# LED_Matrix-2.net
KiCad netlist of a schematic drawn in Altium Designer
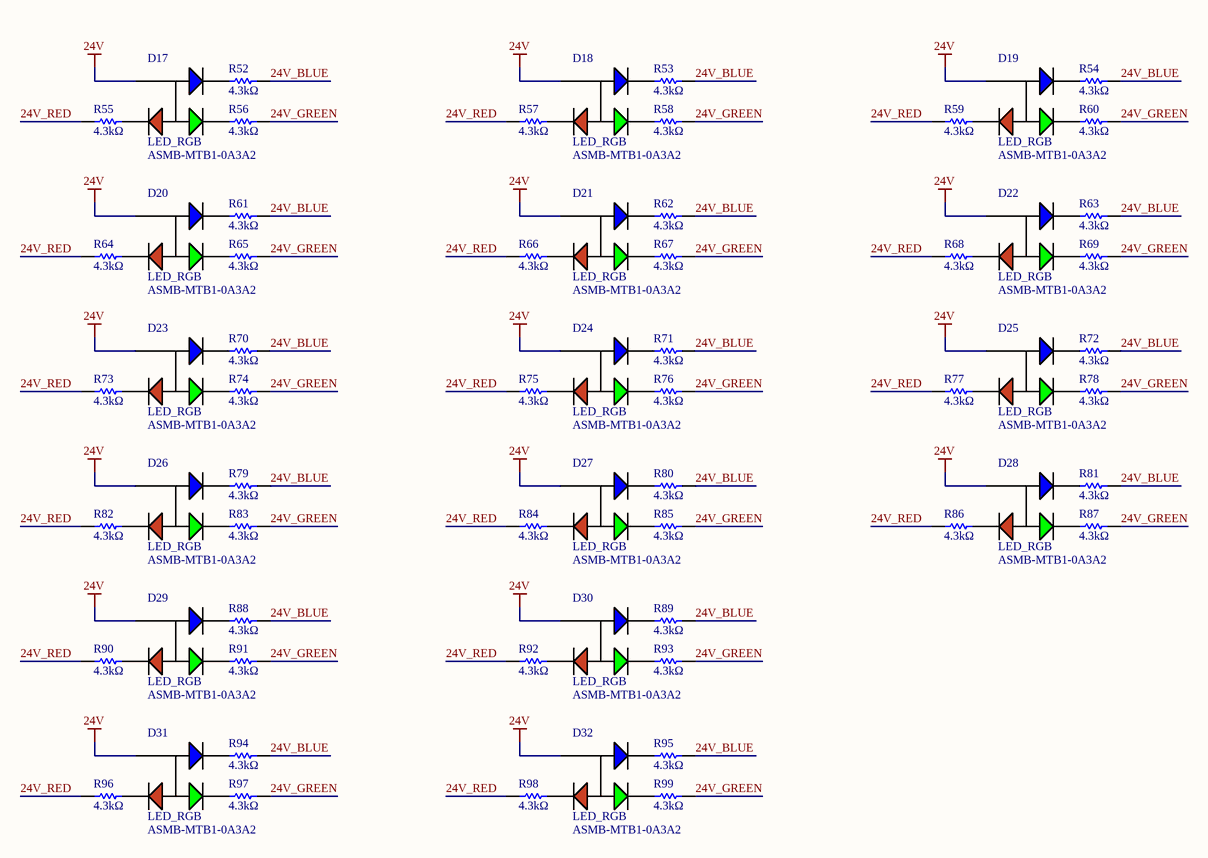
[diagram p0: LED Matrix-2.SchDoc]

(export (version "E")
  (design (tool "Eeschema 10.0.6"))
  (components
    (comp (ref "D17")
      (value "LED_RGB")
      (footprint "LED_RGB")
      (description "LED RGB DIFFUSED 4PLCC SMD")
      (fields (field (name "MANUFACTURER PART NUMBER 1") "ASMB-MTB1-0A3A2"))
      (libsource (lib "UWRT_Schematic_Library_2020") (part "LED_RGB"))
    )
    (comp (ref "D18")
      (value "LED_RGB")
      (footprint "LED_RGB")
      (description "LED RGB DIFFUSED 4PLCC SMD")
      (fields (field (name "MANUFACTURER PART NUMBER 1") "ASMB-MTB1-0A3A2"))
      (libsource (lib "UWRT_Schematic_Library_2020") (part "LED_RGB"))
    )
    (comp (ref "D19")
      (value "LED_RGB")
      (footprint "LED_RGB")
      (description "LED RGB DIFFUSED 4PLCC SMD")
      (fields (field (name "MANUFACTURER PART NUMBER 1") "ASMB-MTB1-0A3A2"))
      (libsource (lib "UWRT_Schematic_Library_2020") (part "LED_RGB"))
    )
    (comp (ref "D20")
      (value "LED_RGB")
      (footprint "LED_RGB")
      (description "LED RGB DIFFUSED 4PLCC SMD")
      (fields (field (name "MANUFACTURER PART NUMBER 1") "ASMB-MTB1-0A3A2"))
      (libsource (lib "UWRT_Schematic_Library_2020") (part "LED_RGB"))
    )
    (comp (ref "D21")
      (value "LED_RGB")
      (footprint "LED_RGB")
      (description "LED RGB DIFFUSED 4PLCC SMD")
      (fields (field (name "MANUFACTURER PART NUMBER 1") "ASMB-MTB1-0A3A2"))
      (libsource (lib "UWRT_Schematic_Library_2020") (part "LED_RGB"))
    )
    (comp (ref "D22")
      (value "LED_RGB")
      (footprint "LED_RGB")
      (description "LED RGB DIFFUSED 4PLCC SMD")
      (fields (field (name "MANUFACTURER PART NUMBER 1") "ASMB-MTB1-0A3A2"))
      (libsource (lib "UWRT_Schematic_Library_2020") (part "LED_RGB"))
    )
    (comp (ref "D23")
      (value "LED_RGB")
      (footprint "LED_RGB")
      (description "LED RGB DIFFUSED 4PLCC SMD")
      (fields (field (name "MANUFACTURER PART NUMBER 1") "ASMB-MTB1-0A3A2"))
      (libsource (lib "UWRT_Schematic_Library_2020") (part "LED_RGB"))
    )
    (comp (ref "D24")
      (value "LED_RGB")
      (footprint "LED_RGB")
      (description "LED RGB DIFFUSED 4PLCC SMD")
      (fields (field (name "MANUFACTURER PART NUMBER 1") "ASMB-MTB1-0A3A2"))
      (libsource (lib "UWRT_Schematic_Library_2020") (part "LED_RGB"))
    )
    (comp (ref "D25")
      (value "LED_RGB")
      (footprint "LED_RGB")
      (description "LED RGB DIFFUSED 4PLCC SMD")
      (fields (field (name "MANUFACTURER PART NUMBER 1") "ASMB-MTB1-0A3A2"))
      (libsource (lib "UWRT_Schematic_Library_2020") (part "LED_RGB"))
    )
    (comp (ref "D26")
      (value "LED_RGB")
      (footprint "LED_RGB")
      (description "LED RGB DIFFUSED 4PLCC SMD")
      (fields (field (name "MANUFACTURER PART NUMBER 1") "ASMB-MTB1-0A3A2"))
      (libsource (lib "UWRT_Schematic_Library_2020") (part "LED_RGB"))
    )
    (comp (ref "D27")
      (value "LED_RGB")
      (footprint "LED_RGB")
      (description "LED RGB DIFFUSED 4PLCC SMD")
      (fields (field (name "MANUFACTURER PART NUMBER 1") "ASMB-MTB1-0A3A2"))
      (libsource (lib "UWRT_Schematic_Library_2020") (part "LED_RGB"))
    )
    (comp (ref "D28")
      (value "LED_RGB")
      (footprint "LED_RGB")
      (description "LED RGB DIFFUSED 4PLCC SMD")
      (fields (field (name "MANUFACTURER PART NUMBER 1") "ASMB-MTB1-0A3A2"))
      (libsource (lib "UWRT_Schematic_Library_2020") (part "LED_RGB"))
    )
    (comp (ref "D29")
      (value "LED_RGB")
      (footprint "LED_RGB")
      (description "LED RGB DIFFUSED 4PLCC SMD")
      (fields (field (name "MANUFACTURER PART NUMBER 1") "ASMB-MTB1-0A3A2"))
      (libsource (lib "UWRT_Schematic_Library_2020") (part "LED_RGB"))
    )
    (comp (ref "D30")
      (value "LED_RGB")
      (footprint "LED_RGB")
      (description "LED RGB DIFFUSED 4PLCC SMD")
      (fields (field (name "MANUFACTURER PART NUMBER 1") "ASMB-MTB1-0A3A2"))
      (libsource (lib "UWRT_Schematic_Library_2020") (part "LED_RGB"))
    )
    (comp (ref "D31")
      (value "LED_RGB")
      (footprint "LED_RGB")
      (description "LED RGB DIFFUSED 4PLCC SMD")
      (fields (field (name "MANUFACTURER PART NUMBER 1") "ASMB-MTB1-0A3A2"))
      (libsource (lib "UWRT_Schematic_Library_2020") (part "LED_RGB"))
    )
    (comp (ref "D32")
      (value "LED_RGB")
      (footprint "LED_RGB")
      (description "LED RGB DIFFUSED 4PLCC SMD")
      (fields (field (name "MANUFACTURER PART NUMBER 1") "ASMB-MTB1-0A3A2"))
      (libsource (lib "UWRT_Schematic_Library_2020") (part "LED_RGB"))
    )
    (comp (ref "R52")
      (value "RES_4.3kΩ_1210_5%")
      (footprint "RES1210")
      (description "RES 4.3K OHM 5% 1/2W 1210")
      (fields (field (name "RESISTANCE") "4.3kΩ") (field (name "TOLERANCE") "5%"))
      (libsource (lib "UWRT_Schematic_Library_2020") (part "RES_4.3kΩ_1210_5%"))
    )
    (comp (ref "R53")
      (value "RES_4.3kΩ_1210_5%")
      (footprint "RES1210")
      (description "RES 4.3K OHM 5% 1/2W 1210")
      (fields (field (name "RESISTANCE") "4.3kΩ") (field (name "TOLERANCE") "5%"))
      (libsource (lib "UWRT_Schematic_Library_2020") (part "RES_4.3kΩ_1210_5%"))
    )
    (comp (ref "R54")
      (value "RES_4.3kΩ_1210_5%")
      (footprint "RES1210")
      (description "RES 4.3K OHM 5% 1/2W 1210")
      (fields (field (name "RESISTANCE") "4.3kΩ") (field (name "TOLERANCE") "5%"))
      (libsource (lib "UWRT_Schematic_Library_2020") (part "RES_4.3kΩ_1210_5%"))
    )
    (comp (ref "R55")
      (value "RES_4.3kΩ_1210_5%")
      (footprint "RES1210")
      (description "RES 4.3K OHM 5% 1/2W 1210")
      (fields (field (name "RESISTANCE") "4.3kΩ") (field (name "TOLERANCE") "5%"))
      (libsource (lib "UWRT_Schematic_Library_2020") (part "RES_4.3kΩ_1210_5%"))
    )
    (comp (ref "R56")
      (value "RES_4.3kΩ_1210_5%")
      (footprint "RES1210")
      (description "RES 4.3K OHM 5% 1/2W 1210")
      (fields (field (name "RESISTANCE") "4.3kΩ") (field (name "TOLERANCE") "5%"))
      (libsource (lib "UWRT_Schematic_Library_2020") (part "RES_4.3kΩ_1210_5%"))
    )
    (comp (ref "R57")
      (value "RES_4.3kΩ_1210_5%")
      (footprint "RES1210")
      (description "RES 4.3K OHM 5% 1/2W 1210")
      (fields (field (name "RESISTANCE") "4.3kΩ") (field (name "TOLERANCE") "5%"))
      (libsource (lib "UWRT_Schematic_Library_2020") (part "RES_4.3kΩ_1210_5%"))
    )
    (comp (ref "R58")
      (value "RES_4.3kΩ_1210_5%")
      (footprint "RES1210")
      (description "RES 4.3K OHM 5% 1/2W 1210")
      (fields (field (name "RESISTANCE") "4.3kΩ") (field (name "TOLERANCE") "5%"))
      (libsource (lib "UWRT_Schematic_Library_2020") (part "RES_4.3kΩ_1210_5%"))
    )
    (comp (ref "R59")
      (value "RES_4.3kΩ_1210_5%")
      (footprint "RES1210")
      (description "RES 4.3K OHM 5% 1/2W 1210")
      (fields (field (name "RESISTANCE") "4.3kΩ") (field (name "TOLERANCE") "5%"))
      (libsource (lib "UWRT_Schematic_Library_2020") (part "RES_4.3kΩ_1210_5%"))
    )
    (comp (ref "R60")
      (value "RES_4.3kΩ_1210_5%")
      (footprint "RES1210")
      (description "RES 4.3K OHM 5% 1/2W 1210")
      (fields (field (name "RESISTANCE") "4.3kΩ") (field (name "TOLERANCE") "5%"))
      (libsource (lib "UWRT_Schematic_Library_2020") (part "RES_4.3kΩ_1210_5%"))
    )
    (comp (ref "R61")
      (value "RES_4.3kΩ_1210_5%")
      (footprint "RES1210")
      (description "RES 4.3K OHM 5% 1/2W 1210")
      (fields (field (name "RESISTANCE") "4.3kΩ") (field (name "TOLERANCE") "5%"))
      (libsource (lib "UWRT_Schematic_Library_2020") (part "RES_4.3kΩ_1210_5%"))
    )
    (comp (ref "R62")
      (value "RES_4.3kΩ_1210_5%")
      (footprint "RES1210")
      (description "RES 4.3K OHM 5% 1/2W 1210")
      (fields (field (name "RESISTANCE") "4.3kΩ") (field (name "TOLERANCE") "5%"))
      (libsource (lib "UWRT_Schematic_Library_2020") (part "RES_4.3kΩ_1210_5%"))
    )
    (comp (ref "R63")
      (value "RES_4.3kΩ_1210_5%")
      (footprint "RES1210")
      (description "RES 4.3K OHM 5% 1/2W 1210")
      (fields (field (name "RESISTANCE") "4.3kΩ") (field (name "TOLERANCE") "5%"))
      (libsource (lib "UWRT_Schematic_Library_2020") (part "RES_4.3kΩ_1210_5%"))
    )
    (comp (ref "R64")
      (value "RES_4.3kΩ_1210_5%")
      (footprint "RES1210")
      (description "RES 4.3K OHM 5% 1/2W 1210")
      (fields (field (name "RESISTANCE") "4.3kΩ") (field (name "TOLERANCE") "5%"))
      (libsource (lib "UWRT_Schematic_Library_2020") (part "RES_4.3kΩ_1210_5%"))
    )
    (comp (ref "R65")
      (value "RES_4.3kΩ_1210_5%")
      (footprint "RES1210")
      (description "RES 4.3K OHM 5% 1/2W 1210")
      (fields (field (name "RESISTANCE") "4.3kΩ") (field (name "TOLERANCE") "5%"))
      (libsource (lib "UWRT_Schematic_Library_2020") (part "RES_4.3kΩ_1210_5%"))
    )
    (comp (ref "R66")
      (value "RES_4.3kΩ_1210_5%")
      (footprint "RES1210")
      (description "RES 4.3K OHM 5% 1/2W 1210")
      (fields (field (name "RESISTANCE") "4.3kΩ") (field (name "TOLERANCE") "5%"))
      (libsource (lib "UWRT_Schematic_Library_2020") (part "RES_4.3kΩ_1210_5%"))
    )
    (comp (ref "R67")
      (value "RES_4.3kΩ_1210_5%")
      (footprint "RES1210")
      (description "RES 4.3K OHM 5% 1/2W 1210")
      (fields (field (name "RESISTANCE") "4.3kΩ") (field (name "TOLERANCE") "5%"))
      (libsource (lib "UWRT_Schematic_Library_2020") (part "RES_4.3kΩ_1210_5%"))
    )
    (comp (ref "R68")
      (value "RES_4.3kΩ_1210_5%")
      (footprint "RES1210")
      (description "RES 4.3K OHM 5% 1/2W 1210")
      (fields (field (name "RESISTANCE") "4.3kΩ") (field (name "TOLERANCE") "5%"))
      (libsource (lib "UWRT_Schematic_Library_2020") (part "RES_4.3kΩ_1210_5%"))
    )
    (comp (ref "R69")
      (value "RES_4.3kΩ_1210_5%")
      (footprint "RES1210")
      (description "RES 4.3K OHM 5% 1/2W 1210")
      (fields (field (name "RESISTANCE") "4.3kΩ") (field (name "TOLERANCE") "5%"))
      (libsource (lib "UWRT_Schematic_Library_2020") (part "RES_4.3kΩ_1210_5%"))
    )
    (comp (ref "R70")
      (value "RES_4.3kΩ_1210_5%")
      (footprint "RES1210")
      (description "RES 4.3K OHM 5% 1/2W 1210")
      (fields (field (name "RESISTANCE") "4.3kΩ") (field (name "TOLERANCE") "5%"))
      (libsource (lib "UWRT_Schematic_Library_2020") (part "RES_4.3kΩ_1210_5%"))
    )
    (comp (ref "R71")
      (value "RES_4.3kΩ_1210_5%")
      (footprint "RES1210")
      (description "RES 4.3K OHM 5% 1/2W 1210")
      (fields (field (name "RESISTANCE") "4.3kΩ") (field (name "TOLERANCE") "5%"))
      (libsource (lib "UWRT_Schematic_Library_2020") (part "RES_4.3kΩ_1210_5%"))
    )
    (comp (ref "R72")
      (value "RES_4.3kΩ_1210_5%")
      (footprint "RES1210")
      (description "RES 4.3K OHM 5% 1/2W 1210")
      (fields (field (name "RESISTANCE") "4.3kΩ") (field (name "TOLERANCE") "5%"))
      (libsource (lib "UWRT_Schematic_Library_2020") (part "RES_4.3kΩ_1210_5%"))
    )
    (comp (ref "R73")
      (value "RES_4.3kΩ_1210_5%")
      (footprint "RES1210")
      (description "RES 4.3K OHM 5% 1/2W 1210")
      (fields (field (name "RESISTANCE") "4.3kΩ") (field (name "TOLERANCE") "5%"))
      (libsource (lib "UWRT_Schematic_Library_2020") (part "RES_4.3kΩ_1210_5%"))
    )
    (comp (ref "R74")
      (value "RES_4.3kΩ_1210_5%")
      (footprint "RES1210")
      (description "RES 4.3K OHM 5% 1/2W 1210")
      (fields (field (name "RESISTANCE") "4.3kΩ") (field (name "TOLERANCE") "5%"))
      (libsource (lib "UWRT_Schematic_Library_2020") (part "RES_4.3kΩ_1210_5%"))
    )
    (comp (ref "R75")
      (value "RES_4.3kΩ_1210_5%")
      (footprint "RES1210")
      (description "RES 4.3K OHM 5% 1/2W 1210")
      (fields (field (name "RESISTANCE") "4.3kΩ") (field (name "TOLERANCE") "5%"))
      (libsource (lib "UWRT_Schematic_Library_2020") (part "RES_4.3kΩ_1210_5%"))
    )
    (comp (ref "R76")
      (value "RES_4.3kΩ_1210_5%")
      (footprint "RES1210")
      (description "RES 4.3K OHM 5% 1/2W 1210")
      (fields (field (name "RESISTANCE") "4.3kΩ") (field (name "TOLERANCE") "5%"))
      (libsource (lib "UWRT_Schematic_Library_2020") (part "RES_4.3kΩ_1210_5%"))
    )
    (comp (ref "R77")
      (value "RES_4.3kΩ_1210_5%")
      (footprint "RES1210")
      (description "RES 4.3K OHM 5% 1/2W 1210")
      (fields (field (name "RESISTANCE") "4.3kΩ") (field (name "TOLERANCE") "5%"))
      (libsource (lib "UWRT_Schematic_Library_2020") (part "RES_4.3kΩ_1210_5%"))
    )
    (comp (ref "R78")
      (value "RES_4.3kΩ_1210_5%")
      (footprint "RES1210")
      (description "RES 4.3K OHM 5% 1/2W 1210")
      (fields (field (name "RESISTANCE") "4.3kΩ") (field (name "TOLERANCE") "5%"))
      (libsource (lib "UWRT_Schematic_Library_2020") (part "RES_4.3kΩ_1210_5%"))
    )
    (comp (ref "R79")
      (value "RES_4.3kΩ_1210_5%")
      (footprint "RES1210")
      (description "RES 4.3K OHM 5% 1/2W 1210")
      (fields (field (name "RESISTANCE") "4.3kΩ") (field (name "TOLERANCE") "5%"))
      (libsource (lib "UWRT_Schematic_Library_2020") (part "RES_4.3kΩ_1210_5%"))
    )
    (comp (ref "R80")
      (value "RES_4.3kΩ_1210_5%")
      (footprint "RES1210")
      (description "RES 4.3K OHM 5% 1/2W 1210")
      (fields (field (name "RESISTANCE") "4.3kΩ") (field (name "TOLERANCE") "5%"))
      (libsource (lib "UWRT_Schematic_Library_2020") (part "RES_4.3kΩ_1210_5%"))
    )
    (comp (ref "R81")
      (value "RES_4.3kΩ_1210_5%")
      (footprint "RES1210")
      (description "RES 4.3K OHM 5% 1/2W 1210")
      (fields (field (name "RESISTANCE") "4.3kΩ") (field (name "TOLERANCE") "5%"))
      (libsource (lib "UWRT_Schematic_Library_2020") (part "RES_4.3kΩ_1210_5%"))
    )
    (comp (ref "R82")
      (value "RES_4.3kΩ_1210_5%")
      (footprint "RES1210")
      (description "RES 4.3K OHM 5% 1/2W 1210")
      (fields (field (name "RESISTANCE") "4.3kΩ") (field (name "TOLERANCE") "5%"))
      (libsource (lib "UWRT_Schematic_Library_2020") (part "RES_4.3kΩ_1210_5%"))
    )
    (comp (ref "R83")
      (value "RES_4.3kΩ_1210_5%")
      (footprint "RES1210")
      (description "RES 4.3K OHM 5% 1/2W 1210")
      (fields (field (name "RESISTANCE") "4.3kΩ") (field (name "TOLERANCE") "5%"))
      (libsource (lib "UWRT_Schematic_Library_2020") (part "RES_4.3kΩ_1210_5%"))
    )
    (comp (ref "R84")
      (value "RES_4.3kΩ_1210_5%")
      (footprint "RES1210")
      (description "RES 4.3K OHM 5% 1/2W 1210")
      (fields (field (name "RESISTANCE") "4.3kΩ") (field (name "TOLERANCE") "5%"))
      (libsource (lib "UWRT_Schematic_Library_2020") (part "RES_4.3kΩ_1210_5%"))
    )
    (comp (ref "R85")
      (value "RES_4.3kΩ_1210_5%")
      (footprint "RES1210")
      (description "RES 4.3K OHM 5% 1/2W 1210")
      (fields (field (name "RESISTANCE") "4.3kΩ") (field (name "TOLERANCE") "5%"))
      (libsource (lib "UWRT_Schematic_Library_2020") (part "RES_4.3kΩ_1210_5%"))
    )
    (comp (ref "R86")
      (value "RES_4.3kΩ_1210_5%")
      (footprint "RES1210")
      (description "RES 4.3K OHM 5% 1/2W 1210")
      (fields (field (name "RESISTANCE") "4.3kΩ") (field (name "TOLERANCE") "5%"))
      (libsource (lib "UWRT_Schematic_Library_2020") (part "RES_4.3kΩ_1210_5%"))
    )
    (comp (ref "R87")
      (value "RES_4.3kΩ_1210_5%")
      (footprint "RES1210")
      (description "RES 4.3K OHM 5% 1/2W 1210")
      (fields (field (name "RESISTANCE") "4.3kΩ") (field (name "TOLERANCE") "5%"))
      (libsource (lib "UWRT_Schematic_Library_2020") (part "RES_4.3kΩ_1210_5%"))
    )
    (comp (ref "R88")
      (value "RES_4.3kΩ_1210_5%")
      (footprint "RES1210")
      (description "RES 4.3K OHM 5% 1/2W 1210")
      (fields (field (name "RESISTANCE") "4.3kΩ") (field (name "TOLERANCE") "5%"))
      (libsource (lib "UWRT_Schematic_Library_2020") (part "RES_4.3kΩ_1210_5%"))
    )
    (comp (ref "R89")
      (value "RES_4.3kΩ_1210_5%")
      (footprint "RES1210")
      (description "RES 4.3K OHM 5% 1/2W 1210")
      (fields (field (name "RESISTANCE") "4.3kΩ") (field (name "TOLERANCE") "5%"))
      (libsource (lib "UWRT_Schematic_Library_2020") (part "RES_4.3kΩ_1210_5%"))
    )
    (comp (ref "R90")
      (value "RES_4.3kΩ_1210_5%")
      (footprint "RES1210")
      (description "RES 4.3K OHM 5% 1/2W 1210")
      (fields (field (name "RESISTANCE") "4.3kΩ") (field (name "TOLERANCE") "5%"))
      (libsource (lib "UWRT_Schematic_Library_2020") (part "RES_4.3kΩ_1210_5%"))
    )
    (comp (ref "R91")
      (value "RES_4.3kΩ_1210_5%")
      (footprint "RES1210")
      (description "RES 4.3K OHM 5% 1/2W 1210")
      (fields (field (name "RESISTANCE") "4.3kΩ") (field (name "TOLERANCE") "5%"))
      (libsource (lib "UWRT_Schematic_Library_2020") (part "RES_4.3kΩ_1210_5%"))
    )
    (comp (ref "R92")
      (value "RES_4.3kΩ_1210_5%")
      (footprint "RES1210")
      (description "RES 4.3K OHM 5% 1/2W 1210")
      (fields (field (name "RESISTANCE") "4.3kΩ") (field (name "TOLERANCE") "5%"))
      (libsource (lib "UWRT_Schematic_Library_2020") (part "RES_4.3kΩ_1210_5%"))
    )
    (comp (ref "R93")
      (value "RES_4.3kΩ_1210_5%")
      (footprint "RES1210")
      (description "RES 4.3K OHM 5% 1/2W 1210")
      (fields (field (name "RESISTANCE") "4.3kΩ") (field (name "TOLERANCE") "5%"))
      (libsource (lib "UWRT_Schematic_Library_2020") (part "RES_4.3kΩ_1210_5%"))
    )
    (comp (ref "R94")
      (value "RES_4.3kΩ_1210_5%")
      (footprint "RES1210")
      (description "RES 4.3K OHM 5% 1/2W 1210")
      (fields (field (name "RESISTANCE") "4.3kΩ") (field (name "TOLERANCE") "5%"))
      (libsource (lib "UWRT_Schematic_Library_2020") (part "RES_4.3kΩ_1210_5%"))
    )
    (comp (ref "R95")
      (value "RES_4.3kΩ_1210_5%")
      (footprint "RES1210")
      (description "RES 4.3K OHM 5% 1/2W 1210")
      (fields (field (name "RESISTANCE") "4.3kΩ") (field (name "TOLERANCE") "5%"))
      (libsource (lib "UWRT_Schematic_Library_2020") (part "RES_4.3kΩ_1210_5%"))
    )
    (comp (ref "R96")
      (value "RES_4.3kΩ_1210_5%")
      (footprint "RES1210")
      (description "RES 4.3K OHM 5% 1/2W 1210")
      (fields (field (name "RESISTANCE") "4.3kΩ") (field (name "TOLERANCE") "5%"))
      (libsource (lib "UWRT_Schematic_Library_2020") (part "RES_4.3kΩ_1210_5%"))
    )
    (comp (ref "R97")
      (value "RES_4.3kΩ_1210_5%")
      (footprint "RES1210")
      (description "RES 4.3K OHM 5% 1/2W 1210")
      (fields (field (name "RESISTANCE") "4.3kΩ") (field (name "TOLERANCE") "5%"))
      (libsource (lib "UWRT_Schematic_Library_2020") (part "RES_4.3kΩ_1210_5%"))
    )
    (comp (ref "R98")
      (value "RES_4.3kΩ_1210_5%")
      (footprint "RES1210")
      (description "RES 4.3K OHM 5% 1/2W 1210")
      (fields (field (name "RESISTANCE") "4.3kΩ") (field (name "TOLERANCE") "5%"))
      (libsource (lib "UWRT_Schematic_Library_2020") (part "RES_4.3kΩ_1210_5%"))
    )
    (comp (ref "R99")
      (value "RES_4.3kΩ_1210_5%")
      (footprint "RES1210")
      (description "RES 4.3K OHM 5% 1/2W 1210")
      (fields (field (name "RESISTANCE") "4.3kΩ") (field (name "TOLERANCE") "5%"))
      (libsource (lib "UWRT_Schematic_Library_2020") (part "RES_4.3kΩ_1210_5%"))
    )
  )
  (nets
    (net (code "1") (name "/24V_BLUE") (class "Default")
      (node (ref "R52") (pin "2") (pinfunction "2_2") (pintype "passive"))
      (node (ref "R53") (pin "2") (pinfunction "2_2") (pintype "passive"))
      (node (ref "R54") (pin "2") (pinfunction "2_2") (pintype "passive"))
      (node (ref "R61") (pin "2") (pinfunction "2_2") (pintype "passive"))
      (node (ref "R62") (pin "2") (pinfunction "2_2") (pintype "passive"))
      (node (ref "R63") (pin "2") (pinfunction "2_2") (pintype "passive"))
      (node (ref "R70") (pin "2") (pinfunction "2_2") (pintype "passive"))
      (node (ref "R71") (pin "2") (pinfunction "2_2") (pintype "passive"))
      (node (ref "R72") (pin "2") (pinfunction "2_2") (pintype "passive"))
      (node (ref "R79") (pin "2") (pinfunction "2_2") (pintype "passive"))
      (node (ref "R80") (pin "2") (pinfunction "2_2") (pintype "passive"))
      (node (ref "R81") (pin "2") (pinfunction "2_2") (pintype "passive"))
      (node (ref "R88") (pin "2") (pinfunction "2_2") (pintype "passive"))
      (node (ref "R89") (pin "2") (pinfunction "2_2") (pintype "passive"))
      (node (ref "R94") (pin "2") (pinfunction "2_2") (pintype "passive"))
      (node (ref "R95") (pin "2") (pinfunction "2_2") (pintype "passive"))
    )
    (net (code "2") (name "/24V_GREEN") (class "Default")
      (node (ref "R56") (pin "2") (pinfunction "2_2") (pintype "passive"))
      (node (ref "R58") (pin "2") (pinfunction "2_2") (pintype "passive"))
      (node (ref "R60") (pin "2") (pinfunction "2_2") (pintype "passive"))
      (node (ref "R65") (pin "2") (pinfunction "2_2") (pintype "passive"))
      (node (ref "R67") (pin "2") (pinfunction "2_2") (pintype "passive"))
      (node (ref "R69") (pin "2") (pinfunction "2_2") (pintype "passive"))
      (node (ref "R74") (pin "2") (pinfunction "2_2") (pintype "passive"))
      (node (ref "R76") (pin "2") (pinfunction "2_2") (pintype "passive"))
      (node (ref "R78") (pin "2") (pinfunction "2_2") (pintype "passive"))
      (node (ref "R83") (pin "2") (pinfunction "2_2") (pintype "passive"))
      (node (ref "R85") (pin "2") (pinfunction "2_2") (pintype "passive"))
      (node (ref "R87") (pin "2") (pinfunction "2_2") (pintype "passive"))
      (node (ref "R91") (pin "2") (pinfunction "2_2") (pintype "passive"))
      (node (ref "R93") (pin "2") (pinfunction "2_2") (pintype "passive"))
      (node (ref "R97") (pin "2") (pinfunction "2_2") (pintype "passive"))
      (node (ref "R99") (pin "2") (pinfunction "2_2") (pintype "passive"))
    )
    (net (code "3") (name "/24V_RED") (class "Default")
      (node (ref "R55") (pin "1") (pinfunction "1_1") (pintype "passive"))
      (node (ref "R57") (pin "1") (pinfunction "1_1") (pintype "passive"))
      (node (ref "R59") (pin "1") (pinfunction "1_1") (pintype "passive"))
      (node (ref "R64") (pin "1") (pinfunction "1_1") (pintype "passive"))
      (node (ref "R66") (pin "1") (pinfunction "1_1") (pintype "passive"))
      (node (ref "R68") (pin "1") (pinfunction "1_1") (pintype "passive"))
      (node (ref "R73") (pin "1") (pinfunction "1_1") (pintype "passive"))
      (node (ref "R75") (pin "1") (pinfunction "1_1") (pintype "passive"))
      (node (ref "R77") (pin "1") (pinfunction "1_1") (pintype "passive"))
      (node (ref "R82") (pin "1") (pinfunction "1_1") (pintype "passive"))
      (node (ref "R84") (pin "1") (pinfunction "1_1") (pintype "passive"))
      (node (ref "R86") (pin "1") (pinfunction "1_1") (pintype "passive"))
      (node (ref "R90") (pin "1") (pinfunction "1_1") (pintype "passive"))
      (node (ref "R92") (pin "1") (pinfunction "1_1") (pintype "passive"))
      (node (ref "R96") (pin "1") (pinfunction "1_1") (pintype "passive"))
      (node (ref "R98") (pin "1") (pinfunction "1_1") (pintype "passive"))
    )
    (net (code "4") (name "24V") (class "Default")
      (node (ref "D17") (pin "4") (pinfunction "COMMON_ANODE_4") (pintype "passive"))
      (node (ref "D18") (pin "4") (pinfunction "COMMON_ANODE_4") (pintype "passive"))
      (node (ref "D19") (pin "4") (pinfunction "COMMON_ANODE_4") (pintype "passive"))
      (node (ref "D20") (pin "4") (pinfunction "COMMON_ANODE_4") (pintype "passive"))
      (node (ref "D21") (pin "4") (pinfunction "COMMON_ANODE_4") (pintype "passive"))
      (node (ref "D22") (pin "4") (pinfunction "COMMON_ANODE_4") (pintype "passive"))
      (node (ref "D23") (pin "4") (pinfunction "COMMON_ANODE_4") (pintype "passive"))
      (node (ref "D24") (pin "4") (pinfunction "COMMON_ANODE_4") (pintype "passive"))
      (node (ref "D25") (pin "4") (pinfunction "COMMON_ANODE_4") (pintype "passive"))
      (node (ref "D26") (pin "4") (pinfunction "COMMON_ANODE_4") (pintype "passive"))
      (node (ref "D27") (pin "4") (pinfunction "COMMON_ANODE_4") (pintype "passive"))
      (node (ref "D28") (pin "4") (pinfunction "COMMON_ANODE_4") (pintype "passive"))
      (node (ref "D29") (pin "4") (pinfunction "COMMON_ANODE_4") (pintype "passive"))
      (node (ref "D30") (pin "4") (pinfunction "COMMON_ANODE_4") (pintype "passive"))
      (node (ref "D31") (pin "4") (pinfunction "COMMON_ANODE_4") (pintype "passive"))
      (node (ref "D32") (pin "4") (pinfunction "COMMON_ANODE_4") (pintype "passive"))
    )
    (net (code "5") (name "Net-(D17-CATHODE_(BLUE))") (class "Default")
      (node (ref "D17") (pin "3") (pinfunction "CATHODE_(BLUE)_3") (pintype "passive"))
      (node (ref "R52") (pin "1") (pinfunction "1_1") (pintype "passive"))
    )
    (net (code "6") (name "Net-(D17-CATHODE_(GREEN))") (class "Default")
      (node (ref "D17") (pin "2") (pinfunction "CATHODE_(GREEN)_2") (pintype "passive"))
      (node (ref "R56") (pin "1") (pinfunction "1_1") (pintype "passive"))
    )
    (net (code "7") (name "Net-(D17-CATHODE_(RED))") (class "Default")
      (node (ref "D17") (pin "1") (pinfunction "CATHODE_(RED)_1") (pintype "passive"))
      (node (ref "R55") (pin "2") (pinfunction "2_2") (pintype "passive"))
    )
    (net (code "8") (name "Net-(D18-CATHODE_(BLUE))") (class "Default")
      (node (ref "D18") (pin "3") (pinfunction "CATHODE_(BLUE)_3") (pintype "passive"))
      (node (ref "R53") (pin "1") (pinfunction "1_1") (pintype "passive"))
    )
    (net (code "9") (name "Net-(D18-CATHODE_(GREEN))") (class "Default")
      (node (ref "D18") (pin "2") (pinfunction "CATHODE_(GREEN)_2") (pintype "passive"))
      (node (ref "R58") (pin "1") (pinfunction "1_1") (pintype "passive"))
    )
    (net (code "10") (name "Net-(D18-CATHODE_(RED))") (class "Default")
      (node (ref "D18") (pin "1") (pinfunction "CATHODE_(RED)_1") (pintype "passive"))
      (node (ref "R57") (pin "2") (pinfunction "2_2") (pintype "passive"))
    )
    (net (code "11") (name "Net-(D19-CATHODE_(BLUE))") (class "Default")
      (node (ref "D19") (pin "3") (pinfunction "CATHODE_(BLUE)_3") (pintype "passive"))
      (node (ref "R54") (pin "1") (pinfunction "1_1") (pintype "passive"))
    )
    (net (code "12") (name "Net-(D19-CATHODE_(GREEN))") (class "Default")
      (node (ref "D19") (pin "2") (pinfunction "CATHODE_(GREEN)_2") (pintype "passive"))
      (node (ref "R60") (pin "1") (pinfunction "1_1") (pintype "passive"))
    )
    (net (code "13") (name "Net-(D19-CATHODE_(RED))") (class "Default")
      (node (ref "D19") (pin "1") (pinfunction "CATHODE_(RED)_1") (pintype "passive"))
      (node (ref "R59") (pin "2") (pinfunction "2_2") (pintype "passive"))
    )
    (net (code "14") (name "Net-(D20-CATHODE_(BLUE))") (class "Default")
      (node (ref "D20") (pin "3") (pinfunction "CATHODE_(BLUE)_3") (pintype "passive"))
      (node (ref "R61") (pin "1") (pinfunction "1_1") (pintype "passive"))
    )
    (net (code "15") (name "Net-(D20-CATHODE_(GREEN))") (class "Default")
      (node (ref "D20") (pin "2") (pinfunction "CATHODE_(GREEN)_2") (pintype "passive"))
      (node (ref "R65") (pin "1") (pinfunction "1_1") (pintype "passive"))
    )
    (net (code "16") (name "Net-(D20-CATHODE_(RED))") (class "Default")
      (node (ref "D20") (pin "1") (pinfunction "CATHODE_(RED)_1") (pintype "passive"))
      (node (ref "R64") (pin "2") (pinfunction "2_2") (pintype "passive"))
    )
    (net (code "17") (name "Net-(D21-CATHODE_(BLUE))") (class "Default")
      (node (ref "D21") (pin "3") (pinfunction "CATHODE_(BLUE)_3") (pintype "passive"))
      (node (ref "R62") (pin "1") (pinfunction "1_1") (pintype "passive"))
    )
    (net (code "18") (name "Net-(D21-CATHODE_(GREEN))") (class "Default")
      (node (ref "D21") (pin "2") (pinfunction "CATHODE_(GREEN)_2") (pintype "passive"))
      (node (ref "R67") (pin "1") (pinfunction "1_1") (pintype "passive"))
    )
    (net (code "19") (name "Net-(D21-CATHODE_(RED))") (class "Default")
      (node (ref "D21") (pin "1") (pinfunction "CATHODE_(RED)_1") (pintype "passive"))
      (node (ref "R66") (pin "2") (pinfunction "2_2") (pintype "passive"))
    )
    (net (code "20") (name "Net-(D22-CATHODE_(BLUE))") (class "Default")
      (node (ref "D22") (pin "3") (pinfunction "CATHODE_(BLUE)_3") (pintype "passive"))
      (node (ref "R63") (pin "1") (pinfunction "1_1") (pintype "passive"))
    )
    (net (code "21") (name "Net-(D22-CATHODE_(GREEN))") (class "Default")
      (node (ref "D22") (pin "2") (pinfunction "CATHODE_(GREEN)_2") (pintype "passive"))
      (node (ref "R69") (pin "1") (pinfunction "1_1") (pintype "passive"))
    )
    (net (code "22") (name "Net-(D22-CATHODE_(RED))") (class "Default")
      (node (ref "D22") (pin "1") (pinfunction "CATHODE_(RED)_1") (pintype "passive"))
      (node (ref "R68") (pin "2") (pinfunction "2_2") (pintype "passive"))
    )
    (net (code "23") (name "Net-(D23-CATHODE_(BLUE))") (class "Default")
      (node (ref "D23") (pin "3") (pinfunction "CATHODE_(BLUE)_3") (pintype "passive"))
      (node (ref "R70") (pin "1") (pinfunction "1_1") (pintype "passive"))
    )
    (net (code "24") (name "Net-(D23-CATHODE_(GREEN))") (class "Default")
      (node (ref "D23") (pin "2") (pinfunction "CATHODE_(GREEN)_2") (pintype "passive"))
      (node (ref "R74") (pin "1") (pinfunction "1_1") (pintype "passive"))
    )
    (net (code "25") (name "Net-(D23-CATHODE_(RED))") (class "Default")
      (node (ref "D23") (pin "1") (pinfunction "CATHODE_(RED)_1") (pintype "passive"))
      (node (ref "R73") (pin "2") (pinfunction "2_2") (pintype "passive"))
    )
    (net (code "26") (name "Net-(D24-CATHODE_(BLUE))") (class "Default")
      (node (ref "D24") (pin "3") (pinfunction "CATHODE_(BLUE)_3") (pintype "passive"))
      (node (ref "R71") (pin "1") (pinfunction "1_1") (pintype "passive"))
    )
    (net (code "27") (name "Net-(D24-CATHODE_(GREEN))") (class "Default")
      (node (ref "D24") (pin "2") (pinfunction "CATHODE_(GREEN)_2") (pintype "passive"))
      (node (ref "R76") (pin "1") (pinfunction "1_1") (pintype "passive"))
    )
    (net (code "28") (name "Net-(D24-CATHODE_(RED))") (class "Default")
      (node (ref "D24") (pin "1") (pinfunction "CATHODE_(RED)_1") (pintype "passive"))
      (node (ref "R75") (pin "2") (pinfunction "2_2") (pintype "passive"))
    )
    (net (code "29") (name "Net-(D25-CATHODE_(BLUE))") (class "Default")
      (node (ref "D25") (pin "3") (pinfunction "CATHODE_(BLUE)_3") (pintype "passive"))
      (node (ref "R72") (pin "1") (pinfunction "1_1") (pintype "passive"))
    )
    (net (code "30") (name "Net-(D25-CATHODE_(GREEN))") (class "Default")
      (node (ref "D25") (pin "2") (pinfunction "CATHODE_(GREEN)_2") (pintype "passive"))
      (node (ref "R78") (pin "1") (pinfunction "1_1") (pintype "passive"))
    )
    (net (code "31") (name "Net-(D25-CATHODE_(RED))") (class "Default")
      (node (ref "D25") (pin "1") (pinfunction "CATHODE_(RED)_1") (pintype "passive"))
      (node (ref "R77") (pin "2") (pinfunction "2_2") (pintype "passive"))
    )
    (net (code "32") (name "Net-(D26-CATHODE_(BLUE))") (class "Default")
      (node (ref "D26") (pin "3") (pinfunction "CATHODE_(BLUE)_3") (pintype "passive"))
      (node (ref "R79") (pin "1") (pinfunction "1_1") (pintype "passive"))
    )
    (net (code "33") (name "Net-(D26-CATHODE_(GREEN))") (class "Default")
      (node (ref "D26") (pin "2") (pinfunction "CATHODE_(GREEN)_2") (pintype "passive"))
      (node (ref "R83") (pin "1") (pinfunction "1_1") (pintype "passive"))
    )
    (net (code "34") (name "Net-(D26-CATHODE_(RED))") (class "Default")
      (node (ref "D26") (pin "1") (pinfunction "CATHODE_(RED)_1") (pintype "passive"))
      (node (ref "R82") (pin "2") (pinfunction "2_2") (pintype "passive"))
    )
    (net (code "35") (name "Net-(D27-CATHODE_(BLUE))") (class "Default")
      (node (ref "D27") (pin "3") (pinfunction "CATHODE_(BLUE)_3") (pintype "passive"))
      (node (ref "R80") (pin "1") (pinfunction "1_1") (pintype "passive"))
    )
    (net (code "36") (name "Net-(D27-CATHODE_(GREEN))") (class "Default")
      (node (ref "D27") (pin "2") (pinfunction "CATHODE_(GREEN)_2") (pintype "passive"))
      (node (ref "R85") (pin "1") (pinfunction "1_1") (pintype "passive"))
    )
    (net (code "37") (name "Net-(D27-CATHODE_(RED))") (class "Default")
      (node (ref "D27") (pin "1") (pinfunction "CATHODE_(RED)_1") (pintype "passive"))
      (node (ref "R84") (pin "2") (pinfunction "2_2") (pintype "passive"))
    )
    (net (code "38") (name "Net-(D28-CATHODE_(BLUE))") (class "Default")
      (node (ref "D28") (pin "3") (pinfunction "CATHODE_(BLUE)_3") (pintype "passive"))
      (node (ref "R81") (pin "1") (pinfunction "1_1") (pintype "passive"))
    )
    (net (code "39") (name "Net-(D28-CATHODE_(GREEN))") (class "Default")
      (node (ref "D28") (pin "2") (pinfunction "CATHODE_(GREEN)_2") (pintype "passive"))
      (node (ref "R87") (pin "1") (pinfunction "1_1") (pintype "passive"))
    )
    (net (code "40") (name "Net-(D28-CATHODE_(RED))") (class "Default")
      (node (ref "D28") (pin "1") (pinfunction "CATHODE_(RED)_1") (pintype "passive"))
      (node (ref "R86") (pin "2") (pinfunction "2_2") (pintype "passive"))
    )
    (net (code "41") (name "Net-(D29-CATHODE_(BLUE))") (class "Default")
      (node (ref "D29") (pin "3") (pinfunction "CATHODE_(BLUE)_3") (pintype "passive"))
      (node (ref "R88") (pin "1") (pinfunction "1_1") (pintype "passive"))
    )
    (net (code "42") (name "Net-(D29-CATHODE_(GREEN))") (class "Default")
      (node (ref "D29") (pin "2") (pinfunction "CATHODE_(GREEN)_2") (pintype "passive"))
      (node (ref "R91") (pin "1") (pinfunction "1_1") (pintype "passive"))
    )
    (net (code "43") (name "Net-(D29-CATHODE_(RED))") (class "Default")
      (node (ref "D29") (pin "1") (pinfunction "CATHODE_(RED)_1") (pintype "passive"))
      (node (ref "R90") (pin "2") (pinfunction "2_2") (pintype "passive"))
    )
    (net (code "44") (name "Net-(D30-CATHODE_(BLUE))") (class "Default")
      (node (ref "D30") (pin "3") (pinfunction "CATHODE_(BLUE)_3") (pintype "passive"))
      (node (ref "R89") (pin "1") (pinfunction "1_1") (pintype "passive"))
    )
    (net (code "45") (name "Net-(D30-CATHODE_(GREEN))") (class "Default")
      (node (ref "D30") (pin "2") (pinfunction "CATHODE_(GREEN)_2") (pintype "passive"))
      (node (ref "R93") (pin "1") (pinfunction "1_1") (pintype "passive"))
    )
    (net (code "46") (name "Net-(D30-CATHODE_(RED))") (class "Default")
      (node (ref "D30") (pin "1") (pinfunction "CATHODE_(RED)_1") (pintype "passive"))
      (node (ref "R92") (pin "2") (pinfunction "2_2") (pintype "passive"))
    )
    (net (code "47") (name "Net-(D31-CATHODE_(BLUE))") (class "Default")
      (node (ref "D31") (pin "3") (pinfunction "CATHODE_(BLUE)_3") (pintype "passive"))
      (node (ref "R94") (pin "1") (pinfunction "1_1") (pintype "passive"))
    )
    (net (code "48") (name "Net-(D31-CATHODE_(GREEN))") (class "Default")
      (node (ref "D31") (pin "2") (pinfunction "CATHODE_(GREEN)_2") (pintype "passive"))
      (node (ref "R97") (pin "1") (pinfunction "1_1") (pintype "passive"))
    )
    (net (code "49") (name "Net-(D31-CATHODE_(RED))") (class "Default")
      (node (ref "D31") (pin "1") (pinfunction "CATHODE_(RED)_1") (pintype "passive"))
      (node (ref "R96") (pin "2") (pinfunction "2_2") (pintype "passive"))
    )
    (net (code "50") (name "Net-(D32-CATHODE_(BLUE))") (class "Default")
      (node (ref "D32") (pin "3") (pinfunction "CATHODE_(BLUE)_3") (pintype "passive"))
      (node (ref "R95") (pin "1") (pinfunction "1_1") (pintype "passive"))
    )
    (net (code "51") (name "Net-(D32-CATHODE_(GREEN))") (class "Default")
      (node (ref "D32") (pin "2") (pinfunction "CATHODE_(GREEN)_2") (pintype "passive"))
      (node (ref "R99") (pin "1") (pinfunction "1_1") (pintype "passive"))
    )
    (net (code "52") (name "Net-(D32-CATHODE_(RED))") (class "Default")
      (node (ref "D32") (pin "1") (pinfunction "CATHODE_(RED)_1") (pintype "passive"))
      (node (ref "R98") (pin "2") (pinfunction "2_2") (pintype "passive"))
    )
  )
)
